# Power.net
KiCad netlist of a schematic drawn in Altium Designer
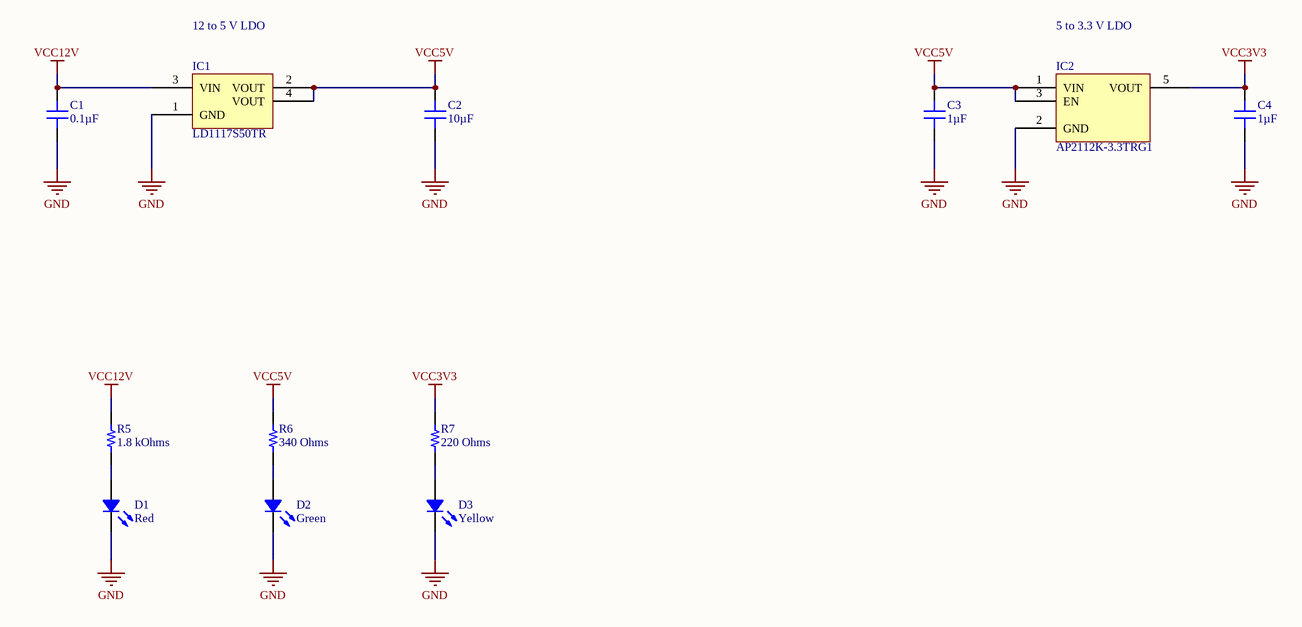
[diagram p0: Power.SchDoc]

(export (version "E")
  (design (tool "Eeschema 10.0.6"))
  (components
    (comp (ref "C1")
      (value "0.1µF")
      (footprint "CAP 0402_1005")
      (description "CAP CER 0.1UF 50V X5R 0402")
      (fields
        (field (name "PART NUMBER") "CGA2B3X5R1H104M050BB")
        (field (name "MANUFACTURER") "TDK Corporation")
      )
      (libsource (lib "Celestial") (part "Capacitor"))
    )
    (comp (ref "C2")
      (value "10µF")
      (footprint "CAP 0805_2012")
      (description "CAP CER 10UF 25V X6S 0805")
      (fields
        (field (name "PART NUMBER") "GRM21BC81E106ME51L")
        (field (name "MANUFACTURER") "Murata Electronics")
      )
      (libsource (lib "Celestial") (part "Capacitor"))
    )
    (comp (ref "C3")
      (value "1µF")
      (footprint "CAP 0402_1005")
      (description "CAP CER 1UF 10V X5R 0402")
      (fields (field (name "PART NUMBER") "0402ZD105KAT4A") (field (name "MANUFACTURER") "AVX Corporation"))
      (libsource (lib "Celestial") (part "Capacitor"))
    )
    (comp (ref "C4")
      (value "1µF")
      (footprint "CAP 0402_1005")
      (description "CAP CER 1UF 10V X5R 0402")
      (fields (field (name "PART NUMBER") "0402ZD105KAT4A") (field (name "MANUFACTURER") "AVX Corporation"))
      (libsource (lib "Celestial") (part "Capacitor"))
    )
    (comp (ref "D1")
      (value "Red")
      (footprint "LED 0603_1608 RED")
      (description "1.64X0.84X1.15MM TOP VIEW SMT LE")
      (fields
        (field (name "PART NUMBER") "SML-LXIL0603SIC-TR")
        (field (name "MANUFACTURER") "Lumex Opto/Components Inc.")
      )
      (libsource (lib "Celestial") (part "LED"))
    )
    (comp (ref "D2")
      (value "Green")
      (footprint "LED 0402_1005 GREEN")
      (description "LED GREEN CLEAR 2SMD")
      (fields
        (field (name "PART NUMBER") "EAST10052GA0")
        (field (name "MANUFACTURER") "Everlight Electronics Co Ltd")
      )
      (libsource (lib "Celestial") (part "LED"))
    )
    (comp (ref "D3")
      (value "Yellow")
      (footprint "LED 0402_1005 YELLOW")
      (description "LED YELLOW CLEAR CHIP SMD")
      (fields (field (name "PART NUMBER") "APG1005SYC-T") (field (name "MANUFACTURER") "Kingbright"))
      (libsource (lib "Celestial") (part "LED"))
    )
    (comp (ref "IC1")
      (value "LD1117S50TR")
      (footprint "ST SOT-223")
      (description "IC REG LINEAR 5V 800MA SOT223")
      (fields (field (name "MANUFACTURER") "STMicroelectronics"))
      (libsource (lib "Celestial") (part "ST LD1117"))
    )
    (comp (ref "IC2")
      (value "AP2112K-3.3TRG1")
      (footprint "DIODES SOT-23-5 W5")
      (description "IC REG LINEAR 3.3V 600MA SOT25")
      (fields (field (name "MANUFACTURER") "Diodes Incorporated"))
      (libsource (lib "Celestial") (part "DIODES INC AP2112K"))
    )
    (comp (ref "R5")
      (value "1.8 kOhms")
      (footprint "RES 0402_1005")
      (description "RES SMD 1.8K OHM 1% 1/16W 0402")
      (fields (field (name "PART NUMBER") "CR0402-FX-1801GLF") (field (name "MANUFACTURER") "Bourns Inc."))
      (libsource (lib "Celestial") (part "Resistor"))
    )
    (comp (ref "R6")
      (value "340 Ohms")
      (footprint "RES 0402_1005")
      (description "RES SMD 340 OHM 1% 1/10W 0402")
      (fields
        (field (name "PART NUMBER") "ERJ-2RKF3400X")
        (field (name "MANUFACTURER") "Panasonic Electronic Components")
      )
      (libsource (lib "CAL") (part "Resistor"))
    )
    (comp (ref "R7")
      (value "220 Ohms")
      (footprint "RES 0402_1005")
      (description "CRGCQ 0402 220R 5%")
      (fields
        (field (name "PART NUMBER") "CRGCQ0402J220R")
        (field (name "MANUFACTURER") "TE Connectivity Passive Product")
      )
      (libsource (lib "CAL") (part "Resistor"))
    )
  )
  (nets
    (net (code "1") (name "GND") (class "Default")
      (node (ref "C1") (pin "1") (pinfunction "1_1") (pintype "passive"))
      (node (ref "C2") (pin "1") (pinfunction "1_1") (pintype "passive"))
      (node (ref "C3") (pin "1") (pinfunction "1_1") (pintype "passive"))
      (node (ref "C4") (pin "1") (pinfunction "1_1") (pintype "passive"))
      (node (ref "D1") (pin "2") (pinfunction "2_2") (pintype "passive"))
      (node (ref "D2") (pin "2") (pinfunction "2_2") (pintype "passive"))
      (node (ref "D3") (pin "2") (pinfunction "2_2") (pintype "passive"))
      (node (ref "IC1") (pin "1") (pinfunction "GND_1") (pintype "passive"))
      (node (ref "IC2") (pin "2") (pinfunction "GND_2") (pintype "passive"))
    )
    (net (code "2") (name "Net-(D1-Pad1)") (class "Default")
      (node (ref "D1") (pin "1") (pinfunction "1_1") (pintype "passive"))
      (node (ref "R5") (pin "2") (pinfunction "2_2") (pintype "passive"))
    )
    (net (code "3") (name "Net-(D2-Pad1)") (class "Default")
      (node (ref "D2") (pin "1") (pinfunction "1_1") (pintype "passive"))
      (node (ref "R6") (pin "1") (pinfunction "1_1") (pintype "passive"))
    )
    (net (code "4") (name "Net-(D3-Pad1)") (class "Default")
      (node (ref "D3") (pin "1") (pinfunction "1_1") (pintype "passive"))
      (node (ref "R7") (pin "1") (pinfunction "1_1") (pintype "passive"))
    )
    (net (code "5") (name "VCC3V3") (class "Default")
      (node (ref "C4") (pin "2") (pinfunction "2_2") (pintype "passive"))
      (node (ref "IC2") (pin "5") (pinfunction "VOUT_5") (pintype "passive"))
      (node (ref "R7") (pin "2") (pinfunction "2_2") (pintype "passive"))
    )
    (net (code "6") (name "VCC5V") (class "Default")
      (node (ref "C2") (pin "2") (pinfunction "2_2") (pintype "passive"))
      (node (ref "C3") (pin "2") (pinfunction "2_2") (pintype "passive"))
      (node (ref "IC1") (pin "2") (pinfunction "VOUT_2") (pintype "passive"))
      (node (ref "IC1") (pin "4") (pinfunction "VOUT_4") (pintype "passive"))
      (node (ref "IC2") (pin "1") (pinfunction "VIN_1") (pintype "passive"))
      (node (ref "IC2") (pin "3") (pinfunction "EN_3") (pintype "passive"))
      (node (ref "R6") (pin "2") (pinfunction "2_2") (pintype "passive"))
    )
    (net (code "7") (name "VCC12V") (class "Default")
      (node (ref "C1") (pin "2") (pinfunction "2_2") (pintype "passive"))
      (node (ref "IC1") (pin "3") (pinfunction "VIN_3") (pintype "passive"))
      (node (ref "R5") (pin "1") (pinfunction "1_1") (pintype "passive"))
    )
  )
)
